# powerblade_3v4.net
KiCad netlist of a schematic drawn in EAGLE
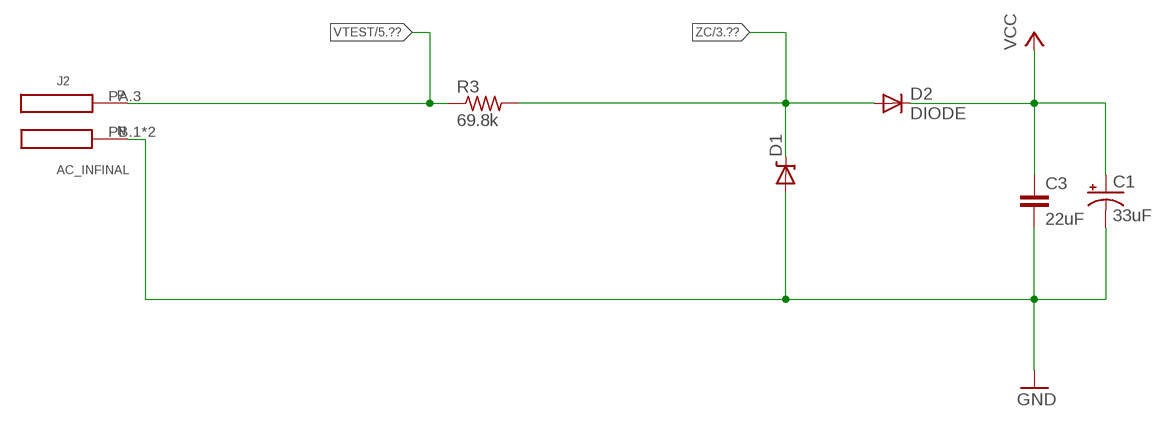
[diagram p0: schematic, sheet 1]
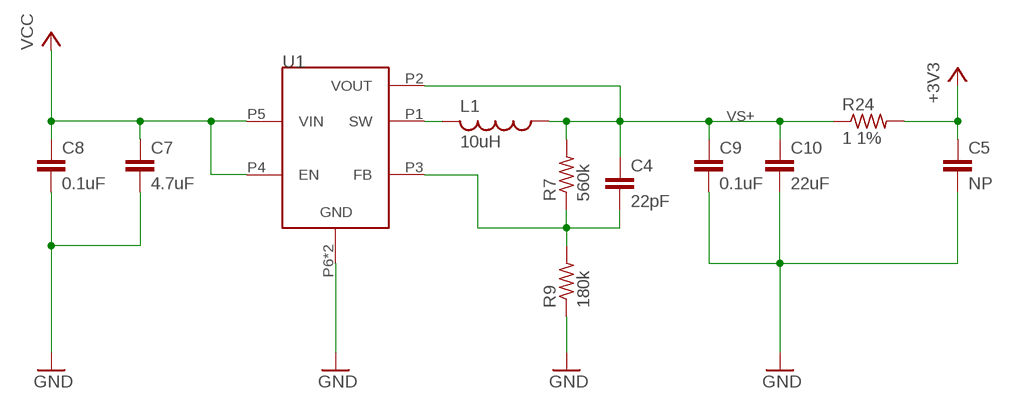
[diagram p1: schematic, sheet 2]
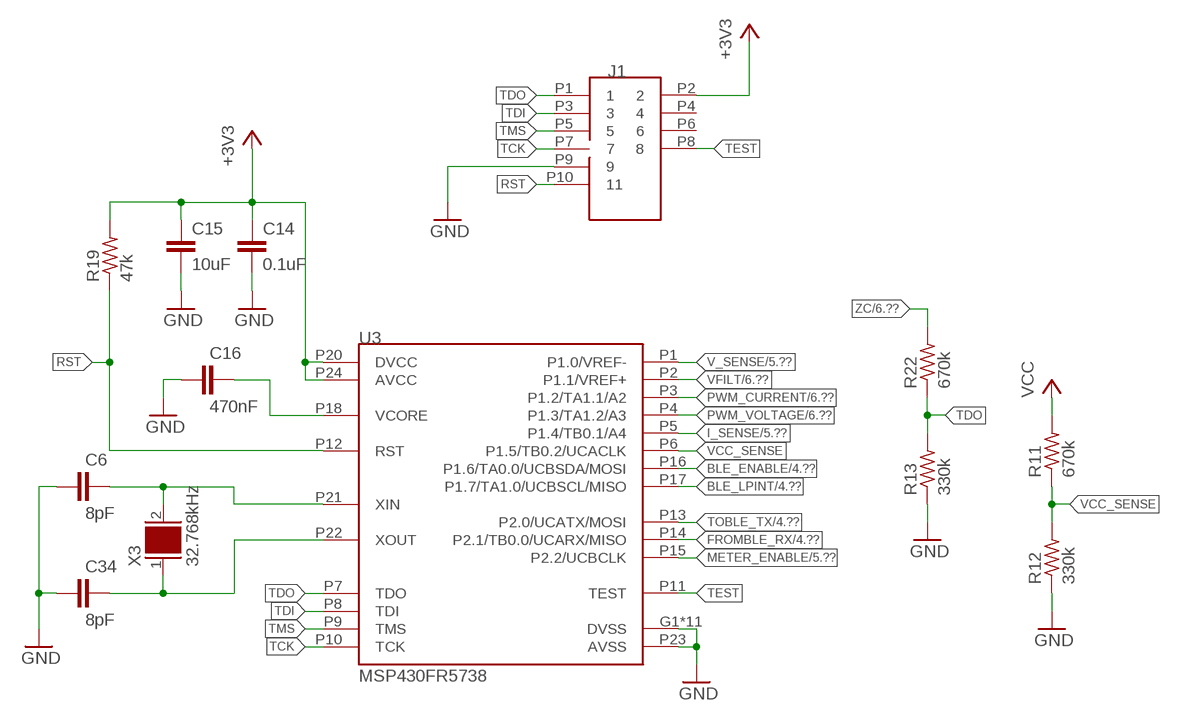
[diagram p2: schematic, sheet 3]
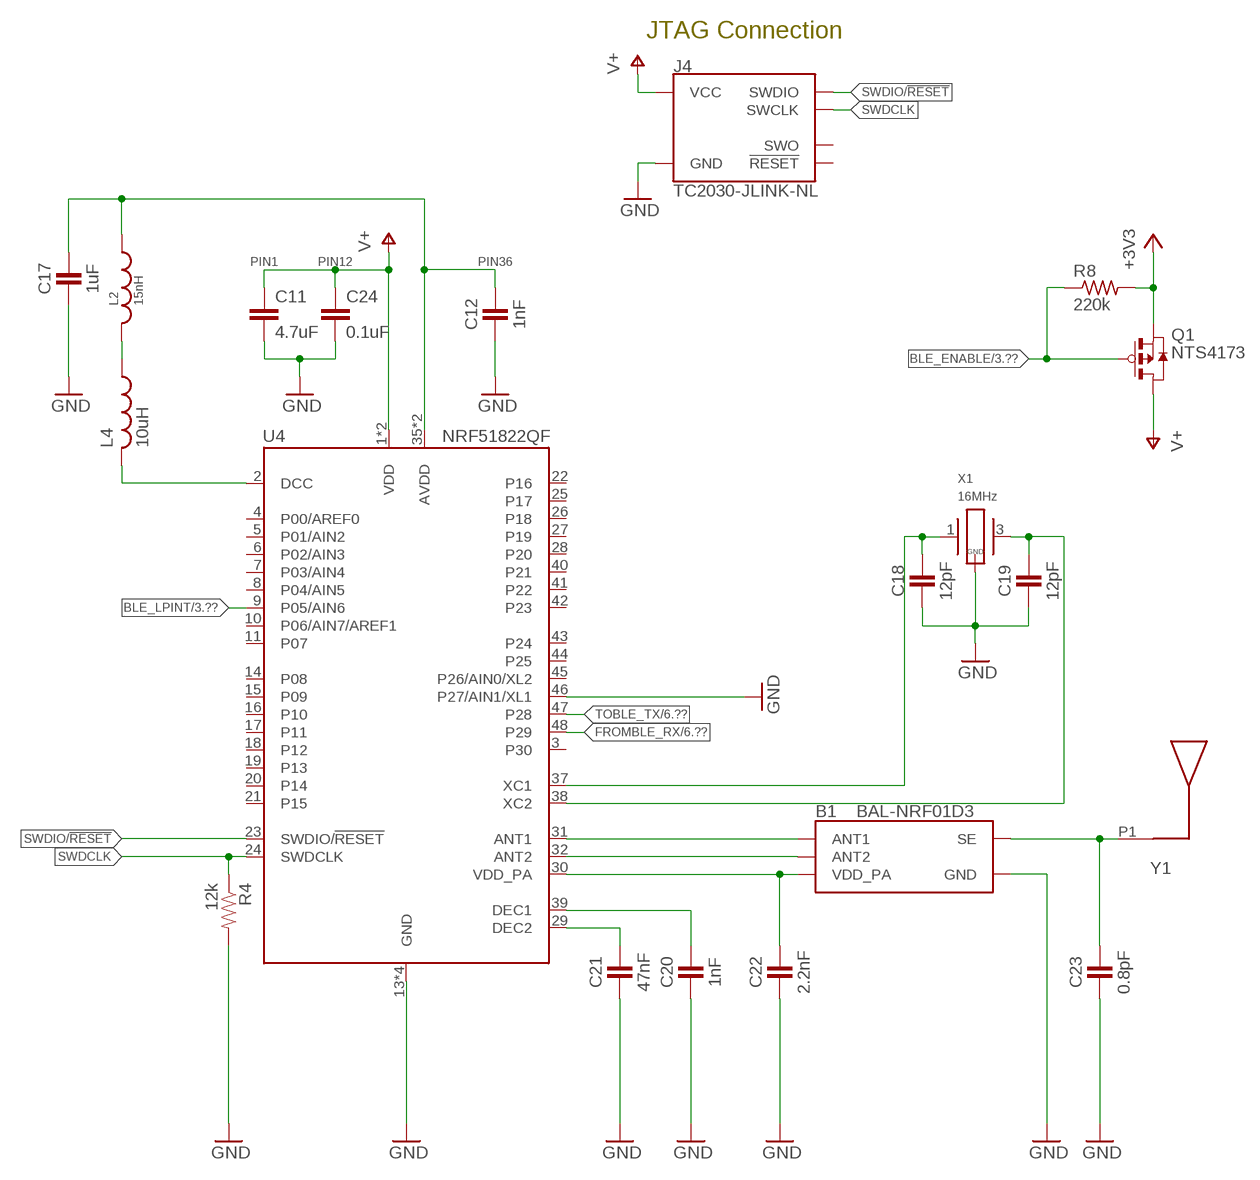
[diagram p3: schematic, sheet 4]
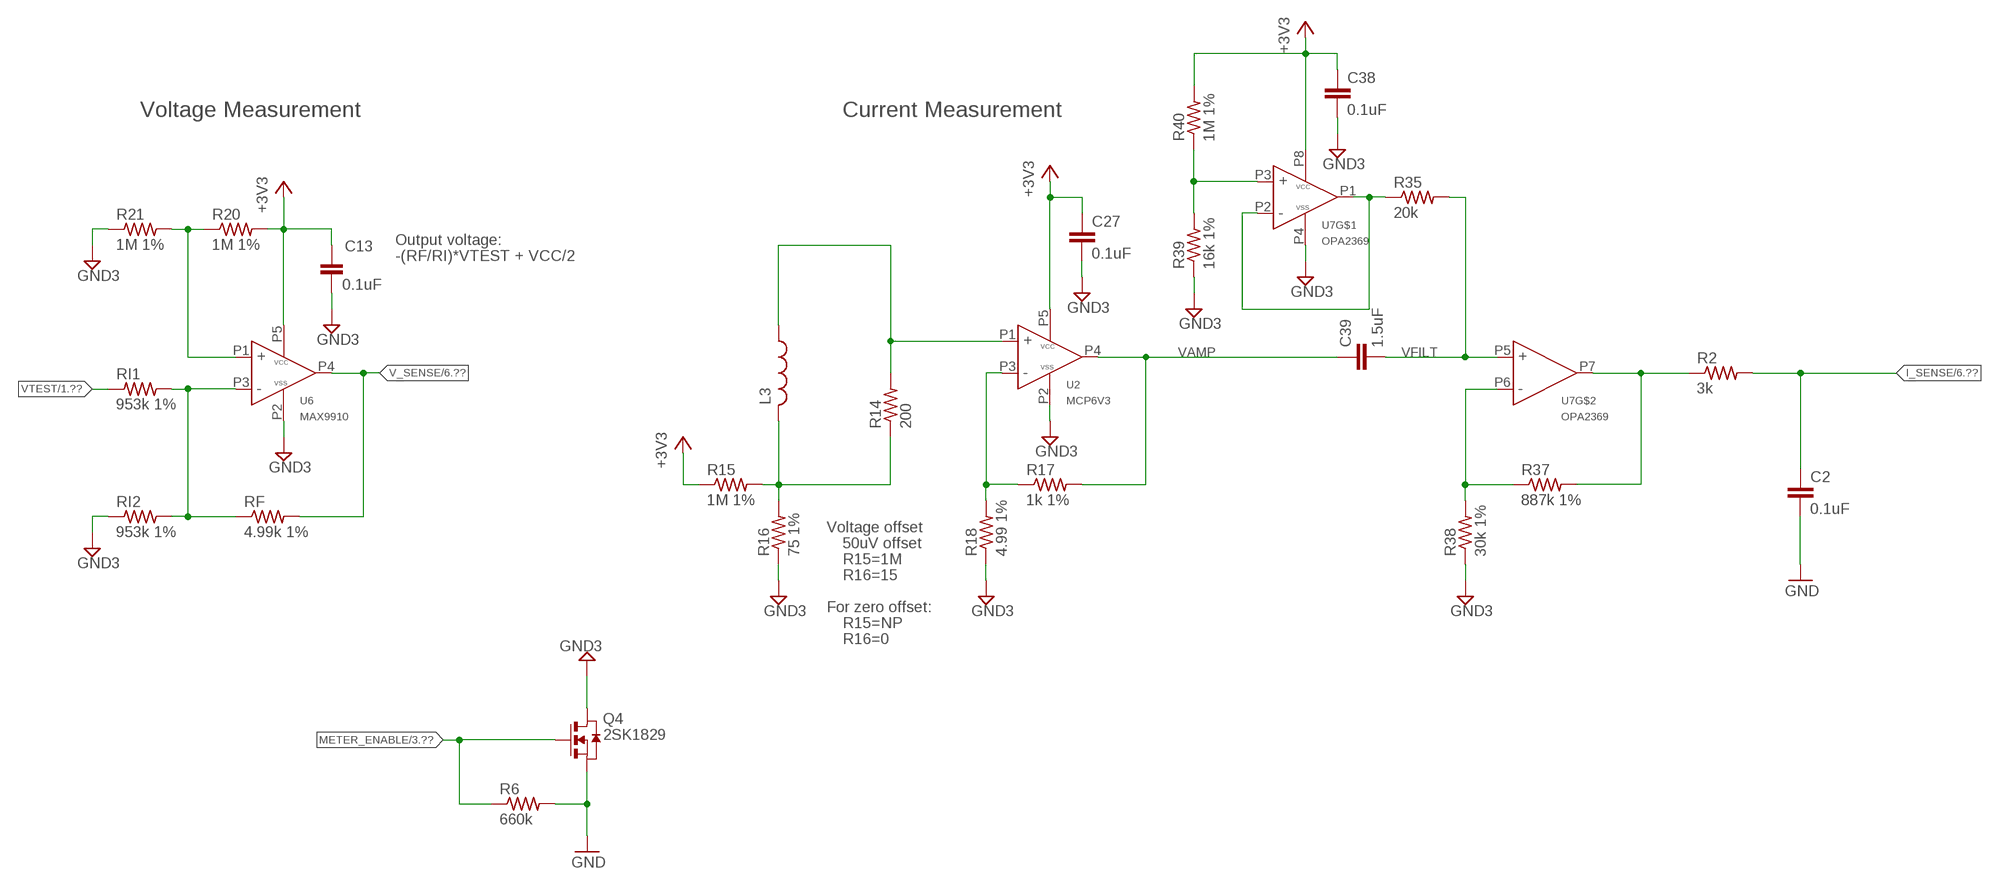
[diagram p4: schematic, sheet 5]
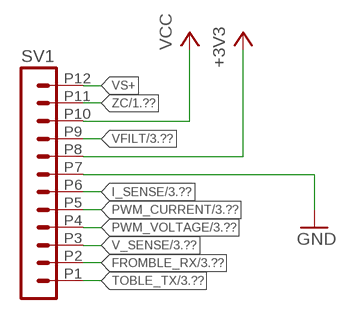
[diagram p5: schematic, sheet 6]

(export (version "E")
  (design (tool "Eeschema 10.0.6"))
  (components
    (comp (ref "SV1")
      (value "MA12-11M27")
      (footprint "eagle-import:MA12-1_1MM27")
      (libsource (lib "eagle-import") (part "MA12-11M27"))
    )
    (comp (ref "B1")
      (value "BAL-NRF01D3")
      (footprint "eagle-import:BAL-NRF01D3")
      (libsource (lib "eagle-import") (part "BAL-NRF01D3"))
    )
    (comp (ref "C11")
      (value "4.7uF")
      (footprint "eagle-import:C0402")
      (libsource (lib "eagle-import") (part "C-EUC0402"))
    )
    (comp (ref "C12")
      (value "1nF")
      (footprint "eagle-import:0402_CAP")
      (libsource (lib "eagle-import") (part "CAPACITOR"))
    )
    (comp (ref "C17")
      (value "1uF")
      (footprint "eagle-import:0402_CAP")
      (libsource (lib "eagle-import") (part "CAPACITOR"))
    )
    (comp (ref "C18")
      (value "12pF")
      (footprint "eagle-import:0402_CAP")
      (libsource (lib "eagle-import") (part "CAPACITOR"))
    )
    (comp (ref "C19")
      (value "12pF")
      (footprint "eagle-import:0402_CAP")
      (libsource (lib "eagle-import") (part "CAPACITOR"))
    )
    (comp (ref "C20")
      (value "1nF")
      (footprint "eagle-import:0402_CAP")
      (libsource (lib "eagle-import") (part "CAPACITOR"))
    )
    (comp (ref "C21")
      (value "47nF")
      (footprint "eagle-import:0402_CAP")
      (libsource (lib "eagle-import") (part "CAPACITOR"))
    )
    (comp (ref "C22")
      (value "2.2nF")
      (footprint "eagle-import:0402_CAP")
      (libsource (lib "eagle-import") (part "CAPACITOR"))
    )
    (comp (ref "C23")
      (value "0.8pF")
      (footprint "eagle-import:0402_CAP")
      (libsource (lib "eagle-import") (part "CAPACITOR"))
    )
    (comp (ref "C24")
      (value "0.1uF")
      (footprint "eagle-import:C0402")
      (libsource (lib "eagle-import") (part "C-EUC0402"))
    )
    (comp (ref "J4")
      (value "TC2030-JLINK-NL")
      (footprint "eagle-import:TC2030-IDC-NL")
      (libsource (lib "eagle-import") (part "TC2030-JLINK-NL"))
    )
    (comp (ref "L2")
      (value "15nH")
      (footprint "eagle-import:0402_CAP")
      (libsource (lib "eagle-import") (part "INDUCTOR0402"))
    )
    (comp (ref "L4")
      (value "10uH")
      (footprint "eagle-import:C0603_TN")
      (libsource (lib "eagle-import") (part "L-USL0603_TN"))
    )
    (comp (ref "Q1")
      (value "NTS4173")
      (footprint "eagle-import:SC-70-3")
      (libsource (lib "eagle-import") (part "NTS4173"))
    )
    (comp (ref "R4")
      (value "12k")
      (footprint "eagle-import:0402_RES")
      (libsource (lib "eagle-import") (part "RESISTOR"))
    )
    (comp (ref "R8")
      (value "220k")
      (footprint "eagle-import:R0402_SM")
      (libsource (lib "eagle-import") (part "R-US_R0402_SM"))
    )
    (comp (ref "U4")
      (value "NRF51822QF")
      (footprint "eagle-import:QFN-48-6MM")
      (libsource (lib "eagle-import") (part "NRF51822QF"))
    )
    (comp (ref "X1")
      (value "16MHz")
      (footprint "eagle-import:TXC-8Y")
      (libsource (lib "eagle-import") (part "TXC-8Y"))
    )
    (comp (ref "Y1")
      (value "UREACH_XTEND")
      (footprint "eagle-import:UREACH_XTEND")
      (libsource (lib "eagle-import") (part "UREACH_XTEND"))
    )
    (comp (ref "C2")
      (value "0.1uF")
      (footprint "eagle-import:C0402")
      (libsource (lib "eagle-import") (part "C-EUC0402"))
    )
    (comp (ref "C13")
      (value "0.1uF")
      (footprint "eagle-import:0402_CAP")
      (libsource (lib "eagle-import") (part "CAPACITOR"))
    )
    (comp (ref "C27")
      (value "0.1uF")
      (footprint "eagle-import:C0402")
      (libsource (lib "eagle-import") (part "C-EUC0402"))
    )
    (comp (ref "C38")
      (value "0.1uF")
      (footprint "eagle-import:C0402")
      (libsource (lib "eagle-import") (part "C-EUC0402"))
    )
    (comp (ref "C39")
      (value "1.5uF")
      (footprint "eagle-import:C0402")
      (libsource (lib "eagle-import") (part "C-EUC0402"))
    )
    (comp (ref "L3")
      (value "L-USL0805")
      (footprint "eagle-import:L0805")
      (libsource (lib "eagle-import") (part "L-USL0805"))
    )
    (comp (ref "Q4")
      (value "2SK1829")
      (footprint "eagle-import:SC-70-3")
      (libsource (lib "eagle-import") (part "2SK1829"))
    )
    (comp (ref "R2")
      (value "3k")
      (footprint "eagle-import:R0402_SM")
      (libsource (lib "eagle-import") (part "R-US_R0402_SM"))
    )
    (comp (ref "R6")
      (value "660k")
      (footprint "eagle-import:R0402")
      (libsource (lib "eagle-import") (part "R-US_R0402"))
    )
    (comp (ref "R14")
      (value "200")
      (footprint "eagle-import:R0402")
      (libsource (lib "eagle-import") (part "R-US_R0402"))
    )
    (comp (ref "R15")
      (value "1M 1%")
      (footprint "eagle-import:R0402")
      (libsource (lib "eagle-import") (part "R-US_R0402"))
    )
    (comp (ref "R16")
      (value "75 1%")
      (footprint "eagle-import:R0402")
      (libsource (lib "eagle-import") (part "R-US_R0402"))
    )
    (comp (ref "R17")
      (value "1k 1%")
      (footprint "eagle-import:R0402")
      (libsource (lib "eagle-import") (part "R-US_R0402"))
    )
    (comp (ref "R18")
      (value "4.99 1%")
      (footprint "eagle-import:R0402")
      (libsource (lib "eagle-import") (part "R-US_R0402"))
    )
    (comp (ref "R20")
      (value "1M 1%")
      (footprint "eagle-import:R0402")
      (libsource (lib "eagle-import") (part "R-US_R0402"))
    )
    (comp (ref "R21")
      (value "1M 1%")
      (footprint "eagle-import:R0402_SM")
      (libsource (lib "eagle-import") (part "R-US_R0402_SM"))
    )
    (comp (ref "R35")
      (value "20k")
      (footprint "eagle-import:R0402")
      (libsource (lib "eagle-import") (part "R-US_R0402"))
    )
    (comp (ref "R37")
      (value "887k 1%")
      (footprint "eagle-import:R0402")
      (libsource (lib "eagle-import") (part "R-US_R0402"))
    )
    (comp (ref "R38")
      (value "30k 1%")
      (footprint "eagle-import:R0402")
      (libsource (lib "eagle-import") (part "R-US_R0402"))
    )
    (comp (ref "R39")
      (value "16k 1%")
      (footprint "eagle-import:R0402")
      (libsource (lib "eagle-import") (part "R-US_R0402"))
    )
    (comp (ref "R40")
      (value "1M 1%")
      (footprint "eagle-import:R0402")
      (libsource (lib "eagle-import") (part "R-US_R0402"))
    )
    (comp (ref "RF")
      (value "4.99k 1%")
      (footprint "eagle-import:R0402")
      (libsource (lib "eagle-import") (part "R-US_R0402"))
    )
    (comp (ref "RI1")
      (value "953k 1%")
      (footprint "eagle-import:R0402")
      (libsource (lib "eagle-import") (part "R-US_R0402"))
    )
    (comp (ref "RI2")
      (value "953k 1%")
      (footprint "eagle-import:R0402")
      (libsource (lib "eagle-import") (part "R-US_R0402"))
    )
    (comp (ref "U2")
      (value "MCP6V3")
      (footprint "eagle-import:SC70-5")
      (fields (field (name "DIGIKEY") "296-19547-1-ND"))
      (libsource (lib "eagle-import") (part "MCP6V3"))
    )
    (comp (ref "U6")
      (value "MAX9910")
      (footprint "eagle-import:SC70-5")
      (fields (field (name "DIGIKEY") "296-25252-1-ND"))
      (libsource (lib "eagle-import") (part "MAX9910"))
    )
    (comp (ref "U7")
      (value "OPA2369")
      (footprint "eagle-import:SOT-23-8")
      (libsource (lib "eagle-import") (part "OPA2369"))
    )
    (comp (ref "C4")
      (value "22pF")
      (footprint "eagle-import:C0402")
      (libsource (lib "eagle-import") (part "C-EUC0402"))
    )
    (comp (ref "C5")
      (value "NP")
      (footprint "eagle-import:C0603_TN")
      (libsource (lib "eagle-import") (part "C-EUC0603_TN"))
    )
    (comp (ref "C7")
      (value "4.7uF")
      (footprint "eagle-import:C0402")
      (libsource (lib "eagle-import") (part "C-EUC0402"))
    )
    (comp (ref "C8")
      (value "0.1uF")
      (footprint "eagle-import:C0402")
      (libsource (lib "eagle-import") (part "C-EUC0402"))
    )
    (comp (ref "C9")
      (value "0.1uF")
      (footprint "eagle-import:C0402_SM")
      (libsource (lib "eagle-import") (part "C-EUC0402_SM"))
    )
    (comp (ref "C10")
      (value "22uF")
      (footprint "eagle-import:C0603_SM")
      (libsource (lib "eagle-import") (part "C-EUC0603_SM"))
    )
    (comp (ref "L1")
      (value "10uH")
      (footprint "eagle-import:L0805")
      (libsource (lib "eagle-import") (part "L-USL0805"))
    )
    (comp (ref "R7")
      (value "560k")
      (footprint "eagle-import:R0402")
      (libsource (lib "eagle-import") (part "R-US_R0402"))
    )
    (comp (ref "R9")
      (value "180k")
      (footprint "eagle-import:R0402")
      (libsource (lib "eagle-import") (part "R-US_R0402"))
    )
    (comp (ref "R24")
      (value "1 1%")
      (footprint "eagle-import:R0603_SM")
      (libsource (lib "eagle-import") (part "R-US_R0603_SM"))
    )
    (comp (ref "U1")
      (value "TPS62122")
      (footprint "eagle-import:WDFN-6")
      (libsource (lib "eagle-import") (part "TPS62122"))
    )
    (comp (ref "C6")
      (value "8pF")
      (footprint "eagle-import:C0402")
      (libsource (lib "eagle-import") (part "C-EUC0402"))
    )
    (comp (ref "C14")
      (value "0.1uF")
      (footprint "eagle-import:C0402")
      (libsource (lib "eagle-import") (part "C-EUC0402"))
    )
    (comp (ref "C15")
      (value "10uF")
      (footprint "eagle-import:C0603_SM")
      (libsource (lib "eagle-import") (part "C-EUC0603_SM"))
    )
    (comp (ref "C16")
      (value "470nF")
      (footprint "eagle-import:C0402")
      (libsource (lib "eagle-import") (part "C-EUC0402"))
    )
    (comp (ref "C34")
      (value "8pF")
      (footprint "eagle-import:C0402")
      (libsource (lib "eagle-import") (part "C-EUC0402"))
    )
    (comp (ref "J1")
      (value "JTAG_14PIN_IDC-ND")
      (footprint "eagle-import:TC2050-IDC-NL-430-ND")
      (libsource (lib "eagle-import") (part "JTAG_14PIN_IDC-ND"))
    )
    (comp (ref "R11")
      (value "670k")
      (footprint "eagle-import:R0402")
      (libsource (lib "eagle-import") (part "R-US_R0402"))
    )
    (comp (ref "R12")
      (value "330k")
      (footprint "eagle-import:R0402")
      (libsource (lib "eagle-import") (part "R-US_R0402"))
    )
    (comp (ref "R13")
      (value "330k")
      (footprint "eagle-import:R0402")
      (libsource (lib "eagle-import") (part "R-US_R0402"))
    )
    (comp (ref "R19")
      (value "47k")
      (footprint "eagle-import:R0402")
      (libsource (lib "eagle-import") (part "R-US_R0402"))
    )
    (comp (ref "R22")
      (value "670k")
      (footprint "eagle-import:R0402")
      (libsource (lib "eagle-import") (part "R-US_R0402"))
    )
    (comp (ref "U3")
      (value "MSP430FR5738")
      (footprint "eagle-import:VQFN-24")
      (libsource (lib "eagle-import") (part "MSP430FR5738"))
    )
    (comp (ref "X3")
      (value "32.768kHz")
      (footprint "eagle-import:0805")
      (libsource (lib "eagle-import") (part "CRYSTAL_0805"))
    )
    (comp (ref "C1")
      (value "33uF")
      (footprint "eagle-import:CPOL0805_SM")
      (libsource (lib "eagle-import") (part "CPOL-US0805_SM"))
    )
    (comp (ref "C3")
      (value "22uF")
      (footprint "eagle-import:C0603_SM")
      (libsource (lib "eagle-import") (part "C-EUC0603_SM"))
    )
    (comp (ref "D1")
      (value "ZENERBZT52")
      (footprint "eagle-import:BZT52")
      (fields (field (name "DIGIKEY") "BZT52C10T-7DICT-ND "))
      (libsource (lib "eagle-import") (part "ZENERBZT52"))
    )
    (comp (ref "D2")
      (value "DIODE")
      (footprint "eagle-import:BAS521")
      (libsource (lib "eagle-import") (part "DIODE"))
    )
    (comp (ref "J2")
      (value "AC_INFINAL")
      (footprint "eagle-import:AC3_FINAL")
      (libsource (lib "eagle-import") (part "AC_INFINAL"))
    )
    (comp (ref "R3")
      (value "69.8k")
      (footprint "eagle-import:R1210")
      (libsource (lib "eagle-import") (part "R-US_R1210"))
    )
  )
  (nets
    (net (code "1") (name "+3V3") (class "Default")
      (node (ref "C13") (pin "1") (pinfunction "1_1") (pintype "bidirectional"))
      (node (ref "C14") (pin "1") (pinfunction "1_1") (pintype "passive"))
      (node (ref "C15") (pin "1") (pinfunction "1_1") (pintype "passive"))
      (node (ref "C27") (pin "1") (pinfunction "1_1") (pintype "passive"))
      (node (ref "C38") (pin "1") (pinfunction "1_1") (pintype "passive"))
      (node (ref "C5") (pin "1") (pinfunction "1_1") (pintype "passive"))
      (node (ref "J1") (pin "P2") (pinfunction "2_P2") (pintype "bidirectional"))
      (node (ref "Q1") (pin "P2") (pinfunction "S_P2") (pintype "passive"))
      (node (ref "R15") (pin "1") (pinfunction "1_1") (pintype "passive"))
      (node (ref "R19") (pin "2") (pinfunction "2_2") (pintype "passive"))
      (node (ref "R20") (pin "2") (pinfunction "2_2") (pintype "passive"))
      (node (ref "R24") (pin "2") (pinfunction "2_2") (pintype "passive"))
      (node (ref "R40") (pin "2") (pinfunction "2_2") (pintype "passive"))
      (node (ref "R8") (pin "2") (pinfunction "2_2") (pintype "passive"))
      (node (ref "SV1") (pin "P8") (pinfunction "8_P8") (pintype "passive"))
      (node (ref "U2") (pin "P5") (pinfunction "VCC_P5") (pintype "bidirectional"))
      (node (ref "U3") (pin "P20") (pinfunction "DVCC_P20") (pintype "bidirectional"))
      (node (ref "U3") (pin "P24") (pinfunction "AVCC_P24") (pintype "bidirectional"))
      (node (ref "U6") (pin "P5") (pinfunction "VCC_P5") (pintype "bidirectional"))
      (node (ref "U7") (pin "P8") (pinfunction "VCC_P8") (pintype "bidirectional"))
    )
    (net (code "2") (name "BLE_ENABLE") (class "Default")
      (node (ref "Q1") (pin "P1") (pinfunction "G_P1") (pintype "passive"))
      (node (ref "R8") (pin "1") (pinfunction "1_1") (pintype "passive"))
      (node (ref "U3") (pin "P16") (pinfunction "P1.6/TA0.0/UCBSDA/MOSI_P16") (pintype "bidirectional"))
    )
    (net (code "3") (name "BLE_LPINT") (class "Default")
      (node (ref "U3") (pin "P17") (pinfunction "P1.7/TA1.0/UCBSCL/MISO_P17") (pintype "bidirectional"))
      (node (ref "U4") (pin "9") (pinfunction "P05/AIN6_9") (pintype "bidirectional"))
    )
    (net (code "4") (name "FROMBLE_RX") (class "Default")
      (node (ref "SV1") (pin "P2") (pinfunction "2_P2") (pintype "passive"))
      (node (ref "U3") (pin "P14") (pinfunction "P2.1/TB0.0/UCARX/MISO_P14") (pintype "bidirectional"))
      (node (ref "U4") (pin "48") (pinfunction "P29_48") (pintype "bidirectional"))
    )
    (net (code "5") (name "GND") (class "Default")
      (node (ref "B1") (pin "GND") (pinfunction "GND_GND") (pintype "bidirectional"))
      (node (ref "C1") (pin "-") (pinfunction "-_-") (pintype "passive"))
      (node (ref "C10") (pin "2") (pinfunction "2_2") (pintype "passive"))
      (node (ref "C11") (pin "2") (pinfunction "2_2") (pintype "passive"))
      (node (ref "C12") (pin "2") (pinfunction "2_2") (pintype "bidirectional"))
      (node (ref "C14") (pin "2") (pinfunction "2_2") (pintype "passive"))
      (node (ref "C15") (pin "2") (pinfunction "2_2") (pintype "passive"))
      (node (ref "C16") (pin "1") (pinfunction "1_1") (pintype "passive"))
      (node (ref "C17") (pin "2") (pinfunction "2_2") (pintype "bidirectional"))
      (node (ref "C18") (pin "2") (pinfunction "2_2") (pintype "bidirectional"))
      (node (ref "C19") (pin "2") (pinfunction "2_2") (pintype "bidirectional"))
      (node (ref "C2") (pin "2") (pinfunction "2_2") (pintype "passive"))
      (node (ref "C20") (pin "2") (pinfunction "2_2") (pintype "bidirectional"))
      (node (ref "C21") (pin "2") (pinfunction "2_2") (pintype "bidirectional"))
      (node (ref "C22") (pin "2") (pinfunction "2_2") (pintype "bidirectional"))
      (node (ref "C23") (pin "2") (pinfunction "2_2") (pintype "bidirectional"))
      (node (ref "C24") (pin "2") (pinfunction "2_2") (pintype "passive"))
      (node (ref "C3") (pin "2") (pinfunction "2_2") (pintype "passive"))
      (node (ref "C34") (pin "1") (pinfunction "1_1") (pintype "passive"))
      (node (ref "C5") (pin "2") (pinfunction "2_2") (pintype "passive"))
      (node (ref "C6") (pin "1") (pinfunction "1_1") (pintype "passive"))
      (node (ref "C7") (pin "2") (pinfunction "2_2") (pintype "passive"))
      (node (ref "C8") (pin "2") (pinfunction "2_2") (pintype "passive"))
      (node (ref "C9") (pin "2") (pinfunction "2_2") (pintype "passive"))
      (node (ref "D1") (pin "A") (pinfunction "A_A") (pintype "passive"))
      (node (ref "J1") (pin "P9") (pinfunction "9_P9") (pintype "bidirectional"))
      (node (ref "J2") (pin "PB.1") (pinfunction "N_PB.1") (pintype "bidirectional"))
      (node (ref "J2") (pin "PB.3") (pinfunction "N_PB.3") (pintype "bidirectional"))
      (node (ref "J4") (pin "5") (pinfunction "GND_5") (pintype "bidirectional"))
      (node (ref "Q4") (pin "P2") (pinfunction "S_P2") (pintype "passive"))
      (node (ref "R12") (pin "1") (pinfunction "1_1") (pintype "passive"))
      (node (ref "R13") (pin "1") (pinfunction "1_1") (pintype "passive"))
      (node (ref "R4") (pin "2") (pinfunction "2_2") (pintype "passive"))
      (node (ref "R6") (pin "2") (pinfunction "2_2") (pintype "passive"))
      (node (ref "R9") (pin "1") (pinfunction "1_1") (pintype "passive"))
      (node (ref "SV1") (pin "P7") (pinfunction "7_P7") (pintype "passive"))
      (node (ref "U1") (pin "P6") (pinfunction "GND_P6") (pintype "bidirectional"))
      (node (ref "U1") (pin "PAD") (pinfunction "GND_PAD") (pintype "bidirectional"))
      (node (ref "U3") (pin "G1") (pinfunction "DVSS_G1") (pintype "bidirectional"))
      (node (ref "U3") (pin "G2") (pinfunction "DVSS_G2") (pintype "bidirectional"))
      (node (ref "U3") (pin "G3") (pinfunction "DVSS_G3") (pintype "bidirectional"))
      (node (ref "U3") (pin "G4") (pinfunction "DVSS_G4") (pintype "bidirectional"))
      (node (ref "U3") (pin "G5") (pinfunction "DVSS_G5") (pintype "bidirectional"))
      (node (ref "U3") (pin "G6") (pinfunction "DVSS_G6") (pintype "bidirectional"))
      (node (ref "U3") (pin "G7") (pinfunction "DVSS_G7") (pintype "bidirectional"))
      (node (ref "U3") (pin "G8") (pinfunction "DVSS_G8") (pintype "bidirectional"))
      (node (ref "U3") (pin "G9") (pinfunction "DVSS_G9") (pintype "bidirectional"))
      (node (ref "U3") (pin "P19") (pinfunction "DVSS_P19") (pintype "bidirectional"))
      (node (ref "U3") (pin "P23") (pinfunction "AVSS_P23") (pintype "bidirectional"))
      (node (ref "U3") (pin "PAD") (pinfunction "DVSS_PAD") (pintype "bidirectional"))
      (node (ref "U4") (pin "13") (pinfunction "GND_13") (pintype "bidirectional"))
      (node (ref "U4") (pin "33") (pinfunction "GND_33") (pintype "bidirectional"))
      (node (ref "U4") (pin "34") (pinfunction "GND_34") (pintype "bidirectional"))
      (node (ref "U4") (pin "46") (pinfunction "P27/AIN1/XL1_46") (pintype "bidirectional"))
      (node (ref "U4") (pin "GND") (pinfunction "GND_GND") (pintype "bidirectional"))
      (node (ref "X1") (pin "2") (pinfunction "GND_2") (pintype "bidirectional"))
      (node (ref "X1") (pin "4") (pinfunction "GND_4") (pintype "bidirectional"))
    )
    (net (code "6") (name "GND3") (class "Default")
      (node (ref "C13") (pin "2") (pinfunction "2_2") (pintype "bidirectional"))
      (node (ref "C27") (pin "2") (pinfunction "2_2") (pintype "passive"))
      (node (ref "C38") (pin "2") (pinfunction "2_2") (pintype "passive"))
      (node (ref "Q4") (pin "P3") (pinfunction "D_P3") (pintype "passive"))
      (node (ref "R16") (pin "1") (pinfunction "1_1") (pintype "passive"))
      (node (ref "R18") (pin "1") (pinfunction "1_1") (pintype "passive"))
      (node (ref "R21") (pin "1") (pinfunction "1_1") (pintype "passive"))
      (node (ref "R38") (pin "1") (pinfunction "1_1") (pintype "passive"))
      (node (ref "R39") (pin "1") (pinfunction "1_1") (pintype "passive"))
      (node (ref "RI2") (pin "1") (pinfunction "1_1") (pintype "passive"))
      (node (ref "U2") (pin "P2") (pinfunction "VSS_P2") (pintype "bidirectional"))
      (node (ref "U6") (pin "P2") (pinfunction "VSS_P2") (pintype "bidirectional"))
      (node (ref "U7") (pin "P4") (pinfunction "VSS_P4") (pintype "bidirectional"))
    )
    (net (code "7") (name "I_SENSE") (class "Default")
      (node (ref "C2") (pin "1") (pinfunction "1_1") (pintype "passive"))
      (node (ref "R2") (pin "2") (pinfunction "2_2") (pintype "passive"))
      (node (ref "SV1") (pin "P6") (pinfunction "6_P6") (pintype "passive"))
      (node (ref "U3") (pin "P5") (pinfunction "P1.4/TB0.1/A4_P5") (pintype "bidirectional"))
    )
    (net (code "8") (name "METER_ENABLE") (class "Default")
      (node (ref "Q4") (pin "P1") (pinfunction "G_P1") (pintype "passive"))
      (node (ref "R6") (pin "1") (pinfunction "1_1") (pintype "passive"))
      (node (ref "U3") (pin "P15") (pinfunction "P2.2/UCBCLK_P15") (pintype "bidirectional"))
    )
    (net (code "9") (name "Net-(B1-PadSE)") (class "Default")
      (node (ref "B1") (pin "SE") (pinfunction "SE_SE") (pintype "bidirectional"))
      (node (ref "C23") (pin "1") (pinfunction "1_1") (pintype "bidirectional"))
      (node (ref "Y1") (pin "P1") (pinfunction "P1_P1") (pintype "bidirectional"))
    )
    (net (code "10") (name "Net-(B1-VDD_PA)") (class "Default")
      (node (ref "B1") (pin "VCC") (pinfunction "VDD_PA_VCC") (pintype "bidirectional"))
      (node (ref "C22") (pin "1") (pinfunction "1_1") (pintype "bidirectional"))
      (node (ref "U4") (pin "30") (pinfunction "VDD_PA_30") (pintype "bidirectional"))
    )
    (net (code "11") (name "Net-(C12-Pad1)") (class "Default")
      (node (ref "C12") (pin "1") (pinfunction "1_1") (pintype "bidirectional"))
      (node (ref "C17") (pin "1") (pinfunction "1_1") (pintype "bidirectional"))
      (node (ref "L2") (pin "1") (pinfunction "1_1") (pintype "bidirectional"))
      (node (ref "U4") (pin "35") (pinfunction "AVDD_35") (pintype "bidirectional"))
      (node (ref "U4") (pin "36") (pinfunction "AVDD_36") (pintype "bidirectional"))
    )
    (net (code "12") (name "Net-(L2-Pad2)") (class "Default")
      (node (ref "L2") (pin "2") (pinfunction "2_2") (pintype "bidirectional"))
      (node (ref "L4") (pin "1") (pinfunction "1_1") (pintype "passive"))
    )
    (net (code "13") (name "Net-(L3-Pad2)") (class "Default")
      (node (ref "L3") (pin "2") (pinfunction "2_2") (pintype "passive"))
      (node (ref "R14") (pin "1") (pinfunction "1_1") (pintype "passive"))
      (node (ref "R15") (pin "2") (pinfunction "2_2") (pintype "passive"))
      (node (ref "R16") (pin "2") (pinfunction "2_2") (pintype "passive"))
    )
    (net (code "14") (name "Net-(U1-FB)") (class "Default")
      (node (ref "C4") (pin "2") (pinfunction "2_2") (pintype "passive"))
      (node (ref "R7") (pin "1") (pinfunction "1_1") (pintype "passive"))
      (node (ref "R9") (pin "2") (pinfunction "2_2") (pintype "passive"))
      (node (ref "U1") (pin "P3") (pinfunction "FB_P3") (pintype "bidirectional"))
    )
    (net (code "15") (name "Net-(U1-SW)") (class "Default")
      (node (ref "L1") (pin "2") (pinfunction "2_2") (pintype "passive"))
      (node (ref "U1") (pin "P1") (pinfunction "SW_P1") (pintype "bidirectional"))
    )
    (net (code "16") (name "Net-(U2-IN+)") (class "Default")
      (node (ref "L3") (pin "1") (pinfunction "1_1") (pintype "passive"))
      (node (ref "R14") (pin "2") (pinfunction "2_2") (pintype "passive"))
      (node (ref "U2") (pin "P1") (pinfunction "IN+_P1") (pintype "bidirectional"))
    )
    (net (code "17") (name "Net-(U2-IN-)") (class "Default")
      (node (ref "R17") (pin "1") (pinfunction "1_1") (pintype "passive"))
      (node (ref "R18") (pin "2") (pinfunction "2_2") (pintype "passive"))
      (node (ref "U2") (pin "P3") (pinfunction "IN-_P3") (pintype "bidirectional"))
    )
    (net (code "18") (name "Net-(U3-VCORE)") (class "Default")
      (node (ref "C16") (pin "2") (pinfunction "2_2") (pintype "passive"))
      (node (ref "U3") (pin "P18") (pinfunction "VCORE_P18") (pintype "bidirectional"))
    )
    (net (code "19") (name "Net-(U3-XIN)") (class "Default")
      (node (ref "C6") (pin "2") (pinfunction "2_2") (pintype "passive"))
      (node (ref "U3") (pin "P21") (pinfunction "XIN_P21") (pintype "bidirectional"))
      (node (ref "X3") (pin "2") (pinfunction "P2_2") (pintype "bidirectional"))
    )
    (net (code "20") (name "Net-(U3-XOUT)") (class "Default")
      (node (ref "C34") (pin "2") (pinfunction "2_2") (pintype "passive"))
      (node (ref "U3") (pin "P22") (pinfunction "XOUT_P22") (pintype "bidirectional"))
      (node (ref "X3") (pin "1") (pinfunction "P1_1") (pintype "bidirectional"))
    )
    (net (code "21") (name "Net-(U4-ANT1)") (class "Default")
      (node (ref "B1") (pin "ANT1") (pinfunction "ANT1_ANT1") (pintype "bidirectional"))
      (node (ref "U4") (pin "31") (pinfunction "ANT1_31") (pintype "bidirectional"))
    )
    (net (code "22") (name "Net-(U4-ANT2)") (class "Default")
      (node (ref "B1") (pin "ANT2") (pinfunction "ANT2_ANT2") (pintype "bidirectional"))
      (node (ref "U4") (pin "32") (pinfunction "ANT2_32") (pintype "bidirectional"))
    )
    (net (code "23") (name "Net-(U4-DCC)") (class "Default")
      (node (ref "L4") (pin "2") (pinfunction "2_2") (pintype "passive"))
      (node (ref "U4") (pin "2") (pinfunction "DCC_2") (pintype "bidirectional"))
    )
    (net (code "24") (name "Net-(U4-DEC1)") (class "Default")
      (node (ref "C20") (pin "1") (pinfunction "1_1") (pintype "bidirectional"))
      (node (ref "U4") (pin "39") (pinfunction "DEC1_39") (pintype "bidirectional"))
    )
    (net (code "25") (name "Net-(U4-DEC2)") (class "Default")
      (node (ref "C21") (pin "1") (pinfunction "1_1") (pintype "bidirectional"))
      (node (ref "U4") (pin "29") (pinfunction "DEC2_29") (pintype "bidirectional"))
    )
    (net (code "26") (name "Net-(U4-XC1)") (class "Default")
      (node (ref "C18") (pin "1") (pinfunction "1_1") (pintype "bidirectional"))
      (node (ref "U4") (pin "37") (pinfunction "XC1_37") (pintype "bidirectional"))
      (node (ref "X1") (pin "1") (pinfunction "1_1") (pintype "bidirectional"))
    )
    (net (code "27") (name "Net-(U4-XC2)") (class "Default")
      (node (ref "C19") (pin "1") (pinfunction "1_1") (pintype "bidirectional"))
      (node (ref "U4") (pin "38") (pinfunction "XC2_38") (pintype "bidirectional"))
      (node (ref "X1") (pin "3") (pinfunction "2_3") (pintype "bidirectional"))
    )
    (net (code "28") (name "Net-(U6-IN+)") (class "Default")
      (node (ref "R20") (pin "1") (pinfunction "1_1") (pintype "passive"))
      (node (ref "R21") (pin "2") (pinfunction "2_2") (pintype "passive"))
      (node (ref "U6") (pin "P1") (pinfunction "IN+_P1") (pintype "bidirectional"))
    )
    (net (code "29") (name "Net-(U6-IN-)") (class "Default")
      (node (ref "RF") (pin "1") (pinfunction "1_1") (pintype "passive"))
      (node (ref "RI1") (pin "2") (pinfunction "2_2") (pintype "passive"))
      (node (ref "RI2") (pin "2") (pinfunction "2_2") (pintype "passive"))
      (node (ref "U6") (pin "P3") (pinfunction "IN-_P3") (pintype "bidirectional"))
    )
    (net (code "30") (name "Net-(U7A-IN+)") (class "Default")
      (node (ref "R39") (pin "2") (pinfunction "2_2") (pintype "passive"))
      (node (ref "R40") (pin "1") (pinfunction "1_1") (pintype "passive"))
      (node (ref "U7") (pin "P3") (pinfunction "IN+_P3") (pintype "bidirectional"))
    )
    (net (code "31") (name "Net-(U7A-IN-)") (class "Default")
      (node (ref "R35") (pin "1") (pinfunction "1_1") (pintype "passive"))
      (node (ref "U7") (pin "P1") (pinfunction "OUT_P1") (pintype "bidirectional"))
      (node (ref "U7") (pin "P2") (pinfunction "IN-_P2") (pintype "bidirectional"))
    )
    (net (code "32") (name "Net-(U7B-IN-)") (class "Default")
      (node (ref "R37") (pin "1") (pinfunction "1_1") (pintype "passive"))
      (node (ref "R38") (pin "2") (pinfunction "2_2") (pintype "passive"))
      (node (ref "U7") (pin "P6") (pinfunction "IN-_P6") (pintype "bidirectional"))
    )
    (net (code "33") (name "Net-(U7B-OUT)") (class "Default")
      (node (ref "R2") (pin "1") (pinfunction "1_1") (pintype "passive"))
      (node (ref "R37") (pin "2") (pinfunction "2_2") (pintype "passive"))
      (node (ref "U7") (pin "P7") (pinfunction "OUT_P7") (pintype "bidirectional"))
    )
    (net (code "34") (name "PWM_CURRENT") (class "Default")
      (node (ref "SV1") (pin "P5") (pinfunction "5_P5") (pintype "passive"))
      (node (ref "U3") (pin "P3") (pinfunction "P1.2/TA1.1/A2_P3") (pintype "bidirectional"))
    )
    (net (code "35") (name "PWM_VOLTAGE") (class "Default")
      (node (ref "SV1") (pin "P4") (pinfunction "4_P4") (pintype "passive"))
      (node (ref "U3") (pin "P4") (pinfunction "P1.3/TA1.2/A3_P4") (pintype "bidirectional"))
    )
    (net (code "36") (name "RST") (class "Default")
      (node (ref "J1") (pin "P10") (pinfunction "11_P10") (pintype "bidirectional"))
      (node (ref "R19") (pin "1") (pinfunction "1_1") (pintype "passive"))
      (node (ref "U3") (pin "P12") (pinfunction "RST_P12") (pintype "bidirectional"))
    )
    (net (code "37") (name "SWDCLK") (class "Default")
      (node (ref "J4") (pin "4") (pinfunction "SWCLK_4") (pintype "bidirectional"))
      (node (ref "R4") (pin "1") (pinfunction "1_1") (pintype "passive"))
      (node (ref "U4") (pin "24") (pinfunction "SWDCLK_24") (pintype "bidirectional"))
    )
    (net (code "38") (name "SWDIO{slash}~{RESET}") (class "Default")
      (node (ref "J4") (pin "2") (pinfunction "SWDIO_2") (pintype "bidirectional"))
      (node (ref "U4") (pin "23") (pinfunction "SWDIO/~{RESET}_23") (pintype "bidirectional"))
    )
    (net (code "39") (name "TCK") (class "Default")
      (node (ref "J1") (pin "P7") (pinfunction "7_P7") (pintype "bidirectional"))
      (node (ref "U3") (pin "P10") (pinfunction "TCK_P10") (pintype "bidirectional"))
    )
    (net (code "40") (name "TDI") (class "Default")
      (node (ref "J1") (pin "P3") (pinfunction "3_P3") (pintype "bidirectional"))
      (node (ref "U3") (pin "P8") (pinfunction "TDI_P8") (pintype "bidirectional"))
    )
    (net (code "41") (name "TDO") (class "Default")
      (node (ref "J1") (pin "P1") (pinfunction "1_P1") (pintype "bidirectional"))
      (node (ref "R13") (pin "2") (pinfunction "2_2") (pintype "passive"))
      (node (ref "R22") (pin "1") (pinfunction "1_1") (pintype "passive"))
      (node (ref "U3") (pin "P7") (pinfunction "TDO_P7") (pintype "bidirectional"))
    )
    (net (code "42") (name "TEST") (class "Default")
      (node (ref "J1") (pin "P8") (pinfunction "8_P8") (pintype "bidirectional"))
      (node (ref "U3") (pin "P11") (pinfunction "TEST_P11") (pintype "bidirectional"))
    )
    (net (code "43") (name "TMS") (class "Default")
      (node (ref "J1") (pin "P5") (pinfunction "5_P5") (pintype "bidirectional"))
      (node (ref "U3") (pin "P9") (pinfunction "TMS_P9") (pintype "bidirectional"))
    )
    (net (code "44") (name "TOBLE_TX") (class "Default")
      (node (ref "SV1") (pin "P1") (pinfunction "1_P1") (pintype "passive"))
      (node (ref "U3") (pin "P13") (pinfunction "P2.0/UCATX/MOSI_P13") (pintype "bidirectional"))
      (node (ref "U4") (pin "47") (pinfunction "P28_47") (pintype "bidirectional"))
    )
    (net (code "45") (name "V+") (class "Default")
      (node (ref "C11") (pin "1") (pinfunction "1_1") (pintype "passive"))
      (node (ref "C24") (pin "1") (pinfunction "1_1") (pintype "passive"))
      (node (ref "J4") (pin "1") (pinfunction "VCC_1") (pintype "bidirectional"))
      (node (ref "Q1") (pin "P3") (pinfunction "D_P3") (pintype "passive"))
      (node (ref "U4") (pin "1") (pinfunction "VDD_1") (pintype "bidirectional"))
      (node (ref "U4") (pin "12") (pinfunction "VDD_12") (pintype "bidirectional"))
    )
    (net (code "46") (name "VAMP") (class "Default")
      (node (ref "C39") (pin "1") (pinfunction "1_1") (pintype "passive"))
      (node (ref "R17") (pin "2") (pinfunction "2_2") (pintype "passive"))
      (node (ref "U2") (pin "P4") (pinfunction "OUT_P4") (pintype "bidirectional"))
    )
    (net (code "47") (name "VCC") (class "Default")
      (node (ref "C1") (pin "+") (pinfunction "+_+") (pintype "passive"))
      (node (ref "C3") (pin "1") (pinfunction "1_1") (pintype "passive"))
      (node (ref "C7") (pin "1") (pinfunction "1_1") (pintype "passive"))
      (node (ref "C8") (pin "1") (pinfunction "1_1") (pintype "passive"))
      (node (ref "D2") (pin "C") (pinfunction "C_C") (pintype "passive"))
      (node (ref "R11") (pin "2") (pinfunction "2_2") (pintype "passive"))
      (node (ref "SV1") (pin "P10") (pinfunction "10_P10") (pintype "passive"))
      (node (ref "U1") (pin "P4") (pinfunction "EN_P4") (pintype "bidirectional"))
      (node (ref "U1") (pin "P5") (pinfunction "VIN_P5") (pintype "bidirectional"))
    )
    (net (code "48") (name "VCC_SENSE") (class "Default")
      (node (ref "R11") (pin "1") (pinfunction "1_1") (pintype "passive"))
      (node (ref "R12") (pin "2") (pinfunction "2_2") (pintype "passive"))
      (node (ref "U3") (pin "P6") (pinfunction "P1.5/TB0.2/UCACLK_P6") (pintype "bidirectional"))
    )
    (net (code "49") (name "VFILT") (class "Default")
      (node (ref "C39") (pin "2") (pinfunction "2_2") (pintype "passive"))
      (node (ref "R35") (pin "2") (pinfunction "2_2") (pintype "passive"))
      (node (ref "SV1") (pin "P9") (pinfunction "9_P9") (pintype "passive"))
      (node (ref "U3") (pin "P2") (pinfunction "P1.1/VREF+_P2") (pintype "bidirectional"))
      (node (ref "U7") (pin "P5") (pinfunction "IN+_P5") (pintype "bidirectional"))
    )
    (net (code "50") (name "VS+") (class "Default")
      (node (ref "C10") (pin "1") (pinfunction "1_1") (pintype "passive"))
      (node (ref "C4") (pin "1") (pinfunction "1_1") (pintype "passive"))
      (node (ref "C9") (pin "1") (pinfunction "1_1") (pintype "passive"))
      (node (ref "L1") (pin "1") (pinfunction "1_1") (pintype "passive"))
      (node (ref "R24") (pin "1") (pinfunction "1_1") (pintype "passive"))
      (node (ref "R7") (pin "2") (pinfunction "2_2") (pintype "passive"))
      (node (ref "SV1") (pin "P12") (pinfunction "12_P12") (pintype "passive"))
      (node (ref "U1") (pin "P2") (pinfunction "VOUT_P2") (pintype "bidirectional"))
    )
    (net (code "51") (name "VTEST") (class "Default")
      (node (ref "J2") (pin "PA.3") (pinfunction "P_PA.3") (pintype "bidirectional"))
      (node (ref "R3") (pin "1") (pinfunction "1_1") (pintype "passive"))
      (node (ref "RI1") (pin "1") (pinfunction "1_1") (pintype "passive"))
    )
    (net (code "52") (name "V_SENSE") (class "Default")
      (node (ref "RF") (pin "2") (pinfunction "2_2") (pintype "passive"))
      (node (ref "SV1") (pin "P3") (pinfunction "3_P3") (pintype "passive"))
      (node (ref "U3") (pin "P1") (pinfunction "P1.0/VREF-_P1") (pintype "bidirectional"))
      (node (ref "U6") (pin "P4") (pinfunction "OUT_P4") (pintype "bidirectional"))
    )
    (net (code "53") (name "ZC") (class "Default")
      (node (ref "D1") (pin "C") (pinfunction "C_C") (pintype "passive"))
      (node (ref "D2") (pin "A") (pinfunction "A_A") (pintype "passive"))
      (node (ref "R22") (pin "2") (pinfunction "2_2") (pintype "passive"))
      (node (ref "R3") (pin "2") (pinfunction "2_2") (pintype "passive"))
      (node (ref "SV1") (pin "P11") (pinfunction "11_P11") (pintype "passive"))
    )
    (net (code "54") (name "unconnected-(J1-4-PadP4)") (class "Default")
      (node (ref "J1") (pin "P4") (pinfunction "4_P4") (pintype "bidirectional"))
    )
    (net (code "55") (name "unconnected-(J1-6-PadP6)") (class "Default")
      (node (ref "J1") (pin "P6") (pinfunction "6_P6") (pintype "bidirectional"))
    )
    (net (code "56") (name "unconnected-(J4-SWO-Pad6)") (class "Default")
      (node (ref "J4") (pin "6") (pinfunction "SWO_6") (pintype "bidirectional"))
    )
    (net (code "57") (name "unconnected-(J4-~{RESET}-Pad3)") (class "Default")
      (node (ref "J4") (pin "3") (pinfunction "~{RESET}_3") (pintype "bidirectional"))
    )
    (net (code "58") (name "unconnected-(U4-P00{slash}AREF0-Pad4)") (class "Default")
      (node (ref "U4") (pin "4") (pinfunction "P00/AREF0_4") (pintype "bidirectional"))
    )
    (net (code "59") (name "unconnected-(U4-P01{slash}AIN2-Pad5)") (class "Default")
      (node (ref "U4") (pin "5") (pinfunction "P01/AIN2_5") (pintype "bidirectional"))
    )
    (net (code "60") (name "unconnected-(U4-P02{slash}AIN3-Pad6)") (class "Default")
      (node (ref "U4") (pin "6") (pinfunction "P02/AIN3_6") (pintype "bidirectional"))
    )
    (net (code "61") (name "unconnected-(U4-P03{slash}AIN4-Pad7)") (class "Default")
      (node (ref "U4") (pin "7") (pinfunction "P03/AIN4_7") (pintype "bidirectional"))
    )
    (net (code "62") (name "unconnected-(U4-P04{slash}AIN5-Pad8)") (class "Default")
      (node (ref "U4") (pin "8") (pinfunction "P04/AIN5_8") (pintype "bidirectional"))
    )
    (net (code "63") (name "unconnected-(U4-P06{slash}AIN7{slash}AREF1-Pad10)") (class "Default")
      (node (ref "U4") (pin "10") (pinfunction "P06/AIN7/AREF1_10") (pintype "bidirectional"))
    )
    (net (code "64") (name "unconnected-(U4-P07-Pad11)") (class "Default")
      (node (ref "U4") (pin "11") (pinfunction "P07_11") (pintype "bidirectional"))
    )
    (net (code "65") (name "unconnected-(U4-P08-Pad14)") (class "Default")
      (node (ref "U4") (pin "14") (pinfunction "P08_14") (pintype "bidirectional"))
    )
    (net (code "66") (name "unconnected-(U4-P09-Pad15)") (class "Default")
      (node (ref "U4") (pin "15") (pinfunction "P09_15") (pintype "bidirectional"))
    )
    (net (code "67") (name "unconnected-(U4-P10-Pad16)") (class "Default")
      (node (ref "U4") (pin "16") (pinfunction "P10_16") (pintype "bidirectional"))
    )
    (net (code "68") (name "unconnected-(U4-P11-Pad17)") (class "Default")
      (node (ref "U4") (pin "17") (pinfunction "P11_17") (pintype "bidirectional"))
    )
    (net (code "69") (name "unconnected-(U4-P12-Pad18)") (class "Default")
      (node (ref "U4") (pin "18") (pinfunction "P12_18") (pintype "bidirectional"))
    )
    (net (code "70") (name "unconnected-(U4-P13-Pad19)") (class "Default")
      (node (ref "U4") (pin "19") (pinfunction "P13_19") (pintype "bidirectional"))
    )
    (net (code "71") (name "unconnected-(U4-P14-Pad20)") (class "Default")
      (node (ref "U4") (pin "20") (pinfunction "P14_20") (pintype "bidirectional"))
    )
    (net (code "72") (name "unconnected-(U4-P15-Pad21)") (class "Default")
      (node (ref "U4") (pin "21") (pinfunction "P15_21") (pintype "bidirectional"))
    )
    (net (code "73") (name "unconnected-(U4-P16-Pad22)") (class "Default")
      (node (ref "U4") (pin "22") (pinfunction "P16_22") (pintype "bidirectional"))
    )
    (net (code "74") (name "unconnected-(U4-P17-Pad25)") (class "Default")
      (node (ref "U4") (pin "25") (pinfunction "P17_25") (pintype "bidirectional"))
    )
    (net (code "75") (name "unconnected-(U4-P18-Pad26)") (class "Default")
      (node (ref "U4") (pin "26") (pinfunction "P18_26") (pintype "bidirectional"))
    )
    (net (code "76") (name "unconnected-(U4-P19-Pad27)") (class "Default")
      (node (ref "U4") (pin "27") (pinfunction "P19_27") (pintype "bidirectional"))
    )
    (net (code "77") (name "unconnected-(U4-P20-Pad28)") (class "Default")
      (node (ref "U4") (pin "28") (pinfunction "P20_28") (pintype "bidirectional"))
    )
    (net (code "78") (name "unconnected-(U4-P21-Pad40)") (class "Default")
      (node (ref "U4") (pin "40") (pinfunction "P21_40") (pintype "bidirectional"))
    )
    (net (code "79") (name "unconnected-(U4-P22-Pad41)") (class "Default")
      (node (ref "U4") (pin "41") (pinfunction "P22_41") (pintype "bidirectional"))
    )
    (net (code "80") (name "unconnected-(U4-P23-Pad42)") (class "Default")
      (node (ref "U4") (pin "42") (pinfunction "P23_42") (pintype "bidirectional"))
    )
    (net (code "81") (name "unconnected-(U4-P24-Pad43)") (class "Default")
      (node (ref "U4") (pin "43") (pinfunction "P24_43") (pintype "bidirectional"))
    )
    (net (code "82") (name "unconnected-(U4-P25-Pad44)") (class "Default")
      (node (ref "U4") (pin "44") (pinfunction "P25_44") (pintype "bidirectional"))
    )
    (net (code "83") (name "unconnected-(U4-P26{slash}AIN0{slash}XL2-Pad45)") (class "Default")
      (node (ref "U4") (pin "45") (pinfunction "P26/AIN0/XL2_45") (pintype "bidirectional"))
    )
    (net (code "84") (name "unconnected-(U4-P30-Pad3)") (class "Default")
      (node (ref "U4") (pin "3") (pinfunction "P30_3") (pintype "bidirectional"))
    )
  )
)
